# nigme3_Potentiom_tres.net
KiCad netlist of a schematic drawn in Altium Designer
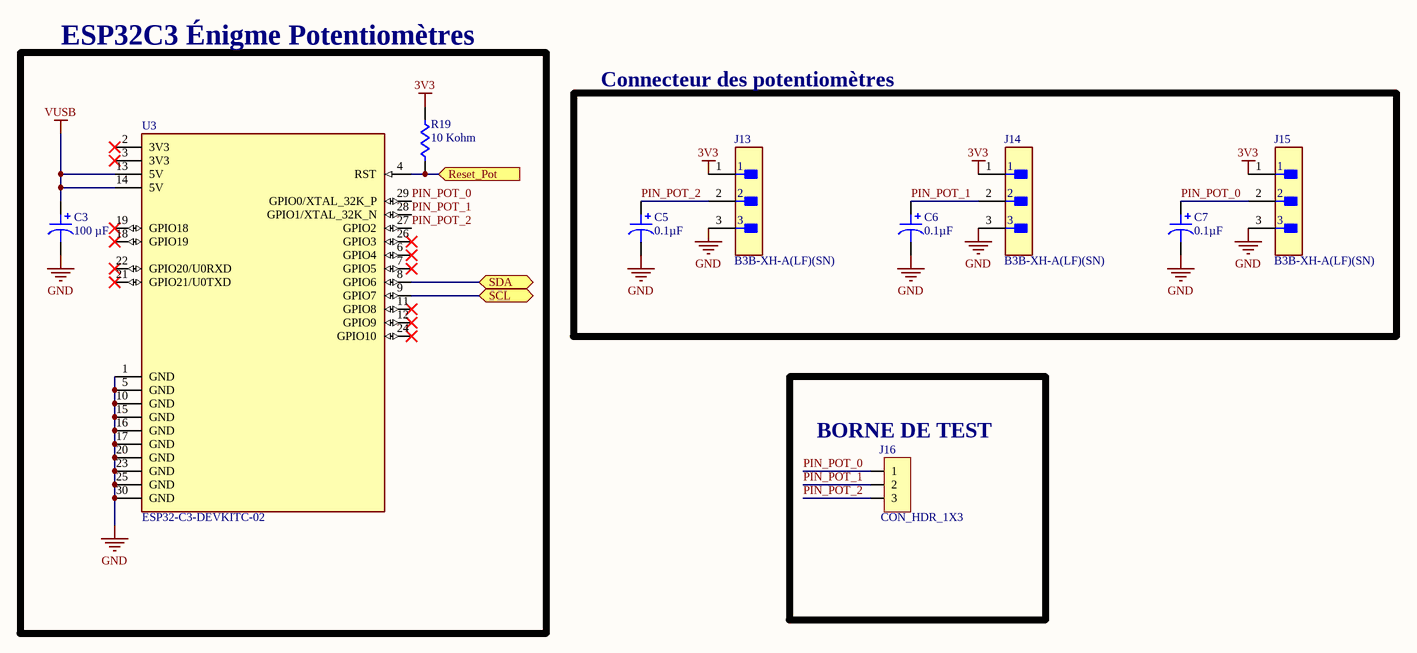
[diagram p0: Énigme3_Potentiomètres.SchDoc]

(export (version "E")
  (design (tool "Eeschema 10.0.6"))
  (components
    (comp (ref "C3")
      (value "100 µF")
      (footprint "CAP AL TH D8 L3.5 H12.5")
      (description "CAP ALUM 100UF 20% 50V RADIAL")
      (fields (field (name "PART NUMBER") "860020674015") (field (name "MANUFACTURER") "Würth Elektronik"))
      (libsource (lib "Celestial Altium Library - altium_library") (part "Polarised Capacitor"))
    )
    (comp (ref "C5")
      (value "0.1µF")
      (footprint "CAP TH ALUM ELEC D5.00mm S2.00mm H12.00mm")
      (description "CAP ALUM 0.1UF 10% 100V RADIAL")
      (fields (field (name "PART NUMBER") "UKL2A0R1KDD") (field (name "MANUFACTURER") "Nichicon"))
      (libsource (lib "Celestial Altium Library - altium_library") (part "Polarised Capacitor"))
    )
    (comp (ref "C6")
      (value "0.1µF")
      (footprint "CAP TH ALUM ELEC D5.00mm S2.00mm H12.00mm")
      (description "CAP ALUM 0.1UF 10% 100V RADIAL")
      (fields (field (name "PART NUMBER") "UKL2A0R1KDD") (field (name "MANUFACTURER") "Nichicon"))
      (libsource (lib "Celestial Altium Library - altium_library") (part "Polarised Capacitor"))
    )
    (comp (ref "C7")
      (value "0.1µF")
      (footprint "CAP TH ALUM ELEC D5.00mm S2.00mm H12.00mm")
      (description "CAP ALUM 0.1UF 10% 100V RADIAL")
      (fields (field (name "PART NUMBER") "UKL2A0R1KDD") (field (name "MANUFACTURER") "Nichicon"))
      (libsource (lib "Celestial Altium Library - altium_library") (part "Polarised Capacitor"))
    )
    (comp (ref "J13")
      (value "B3B-XH-A(LF)(SN)")
      (footprint "FP-B3B-XH-A_LF_SN-MFG")
      (description "CONN HEADER VERT 3POS 2.5MM")
      (libsource (lib "Altium Content Vault") (part "0d3f023dd272f625e17a2be33dea85f"))
    )
    (comp (ref "J14")
      (value "B3B-XH-A(LF)(SN)")
      (footprint "FP-B3B-XH-A_LF_SN-MFG")
      (description "CONN HEADER VERT 3POS 2.5MM")
      (libsource (lib "Altium Content Vault") (part "0d3f023dd272f625e17a2be33dea85f"))
    )
    (comp (ref "J15")
      (value "B3B-XH-A(LF)(SN)")
      (footprint "FP-B3B-XH-A_LF_SN-MFG")
      (description "CONN HEADER VERT 3POS 2.5MM")
      (libsource (lib "Altium Content Vault") (part "0d3f023dd272f625e17a2be33dea85f"))
    )
    (comp (ref "J16")
      (value "CON_HDR_1X3")
      (footprint "CON_HDR_1x3")
      (description "CON - Header 1x3 pins-100Mils - TH")
      (fields (field (name "SOURCE") "CEGEP_SHERBROOKE_TGE_LIBRARY.SchLib"))
      (libsource (lib "Cegep de Sherbrooke") (part "CON_HDR_1X3"))
    )
    (comp (ref "R19")
      (value "10 Kohm")
      (footprint "Res_Template")
      (description "Custom Semiconductor Resistor")
      (libsource (lib "Schlib1") (part "470 ohm"))
    )
    (comp (ref "U3")
      (value "ESP32-C3-DEVKITC-02")
      (footprint "XCVR_ESP32-C3-DEVKITC-02")
      (fields (field (name "MP") "ESP32-C3-DevKitC-02") (field (name "MF") "Espressif Systems"))
      (libsource (lib "ESP32-C3-DEVKITC-02") (part "ESP32-C3-DEVKITC-02"))
    )
  )
  (nets
    (net (code "1") (name "/PIN_POT_0") (class "Default")
      (node (ref "C7") (pin "1") (pinfunction "1_1") (pintype "passive"))
      (node (ref "J15") (pin "2") (pinfunction "2_2") (pintype "passive"))
      (node (ref "J16") (pin "1") (pinfunction "1_1") (pintype "passive"))
      (node (ref "U3") (pin "29") (pinfunction "GPIO0/XTAL_32K_P_29") (pintype "bidirectional"))
    )
    (net (code "2") (name "/PIN_POT_1") (class "Default")
      (node (ref "C6") (pin "1") (pinfunction "1_1") (pintype "passive"))
      (node (ref "J14") (pin "2") (pinfunction "2_2") (pintype "passive"))
      (node (ref "J16") (pin "2") (pinfunction "2_2") (pintype "passive"))
      (node (ref "U3") (pin "28") (pinfunction "GPIO1/XTAL_32K_N_28") (pintype "bidirectional"))
    )
    (net (code "3") (name "/PIN_POT_2") (class "Default")
      (node (ref "C5") (pin "1") (pinfunction "1_1") (pintype "passive"))
      (node (ref "J13") (pin "2") (pinfunction "2_2") (pintype "passive"))
      (node (ref "J16") (pin "3") (pinfunction "3_3") (pintype "passive"))
      (node (ref "U3") (pin "27") (pinfunction "GPIO2_27") (pintype "bidirectional"))
    )
    (net (code "4") (name "/Reset_Pot") (class "Default")
      (node (ref "R19") (pin "1") (pinfunction "1_1") (pintype "passive"))
      (node (ref "U3") (pin "4") (pinfunction "RST_4") (pintype "input"))
    )
    (net (code "5") (name "/SCL") (class "Default")
      (node (ref "U3") (pin "9") (pinfunction "GPIO7_9") (pintype "bidirectional"))
    )
    (net (code "6") (name "/SDA") (class "Default")
      (node (ref "U3") (pin "8") (pinfunction "GPIO6_8") (pintype "bidirectional"))
    )
    (net (code "7") (name "3V3") (class "Default")
      (node (ref "J13") (pin "1") (pinfunction "1_1") (pintype "passive"))
      (node (ref "J14") (pin "1") (pinfunction "1_1") (pintype "passive"))
      (node (ref "J15") (pin "1") (pinfunction "1_1") (pintype "passive"))
      (node (ref "R19") (pin "2") (pinfunction "2_2") (pintype "passive"))
    )
    (net (code "8") (name "GND") (class "Default")
      (node (ref "C3") (pin "2") (pinfunction "2_2") (pintype "passive"))
      (node (ref "C5") (pin "2") (pinfunction "2_2") (pintype "passive"))
      (node (ref "C6") (pin "2") (pinfunction "2_2") (pintype "passive"))
      (node (ref "C7") (pin "2") (pinfunction "2_2") (pintype "passive"))
      (node (ref "J13") (pin "3") (pinfunction "3_3") (pintype "passive"))
      (node (ref "J14") (pin "3") (pinfunction "3_3") (pintype "passive"))
      (node (ref "J15") (pin "3") (pinfunction "3_3") (pintype "passive"))
      (node (ref "U3") (pin "1") (pinfunction "GND_1") (pintype "power_in"))
      (node (ref "U3") (pin "10") (pinfunction "GND_10") (pintype "power_in"))
      (node (ref "U3") (pin "15") (pinfunction "GND_15") (pintype "power_in"))
      (node (ref "U3") (pin "16") (pinfunction "GND_16") (pintype "power_in"))
      (node (ref "U3") (pin "17") (pinfunction "GND_17") (pintype "power_in"))
      (node (ref "U3") (pin "20") (pinfunction "GND_20") (pintype "power_in"))
      (node (ref "U3") (pin "23") (pinfunction "GND_23") (pintype "power_in"))
      (node (ref "U3") (pin "25") (pinfunction "GND_25") (pintype "power_in"))
      (node (ref "U3") (pin "30") (pinfunction "GND_30") (pintype "power_in"))
      (node (ref "U3") (pin "5") (pinfunction "GND_5") (pintype "power_in"))
    )
    (net (code "9") (name "VUSB") (class "Default")
      (node (ref "C3") (pin "1") (pinfunction "1_1") (pintype "passive"))
      (node (ref "U3") (pin "13") (pinfunction "5V_13") (pintype "power_in"))
      (node (ref "U3") (pin "14") (pinfunction "5V_14") (pintype "power_in"))
    )
    (net (code "10") (name "unconnected-(U3-3V3-Pad2)") (class "Default")
      (node (ref "U3") (pin "2") (pinfunction "3V3_2") (pintype "power_in+no_connect"))
    )
    (net (code "11") (name "unconnected-(U3-3V3-Pad3)") (class "Default")
      (node (ref "U3") (pin "3") (pinfunction "3V3_3") (pintype "power_in+no_connect"))
    )
    (net (code "12") (name "unconnected-(U3-GPIO3-Pad26)") (class "Default")
      (node (ref "U3") (pin "26") (pinfunction "GPIO3_26") (pintype "bidirectional+no_connect"))
    )
    (net (code "13") (name "unconnected-(U3-GPIO4-Pad6)") (class "Default")
      (node (ref "U3") (pin "6") (pinfunction "GPIO4_6") (pintype "bidirectional+no_connect"))
    )
    (net (code "14") (name "unconnected-(U3-GPIO5-Pad7)") (class "Default")
      (node (ref "U3") (pin "7") (pinfunction "GPIO5_7") (pintype "bidirectional+no_connect"))
    )
    (net (code "15") (name "unconnected-(U3-GPIO8-Pad11)") (class "Default")
      (node (ref "U3") (pin "11") (pinfunction "GPIO8_11") (pintype "bidirectional+no_connect"))
    )
    (net (code "16") (name "unconnected-(U3-GPIO9-Pad12)") (class "Default")
      (node (ref "U3") (pin "12") (pinfunction "GPIO9_12") (pintype "bidirectional+no_connect"))
    )
    (net (code "17") (name "unconnected-(U3-GPIO10-Pad24)") (class "Default")
      (node (ref "U3") (pin "24") (pinfunction "GPIO10_24") (pintype "bidirectional+no_connect"))
    )
    (net (code "18") (name "unconnected-(U3-GPIO18-Pad19)") (class "Default")
      (node (ref "U3") (pin "19") (pinfunction "GPIO18_19") (pintype "bidirectional+no_connect"))
    )
    (net (code "19") (name "unconnected-(U3-GPIO19-Pad18)") (class "Default")
      (node (ref "U3") (pin "18") (pinfunction "GPIO19_18") (pintype "bidirectional+no_connect"))
    )
    (net (code "20") (name "unconnected-(U3-GPIO20{slash}U0RXD-Pad22)") (class "Default")
      (node (ref "U3") (pin "22") (pinfunction "GPIO20/U0RXD_22") (pintype "bidirectional+no_connect"))
    )
    (net (code "21") (name "unconnected-(U3-GPIO21{slash}U0TXD-Pad21)") (class "Default")
      (node (ref "U3") (pin "21") (pinfunction "GPIO21/U0TXD_21") (pintype "bidirectional+no_connect"))
    )
  )
)
